# MCU009B_Xds100v2Emu.net
KiCad netlist of a schematic drawn in Altium Designer
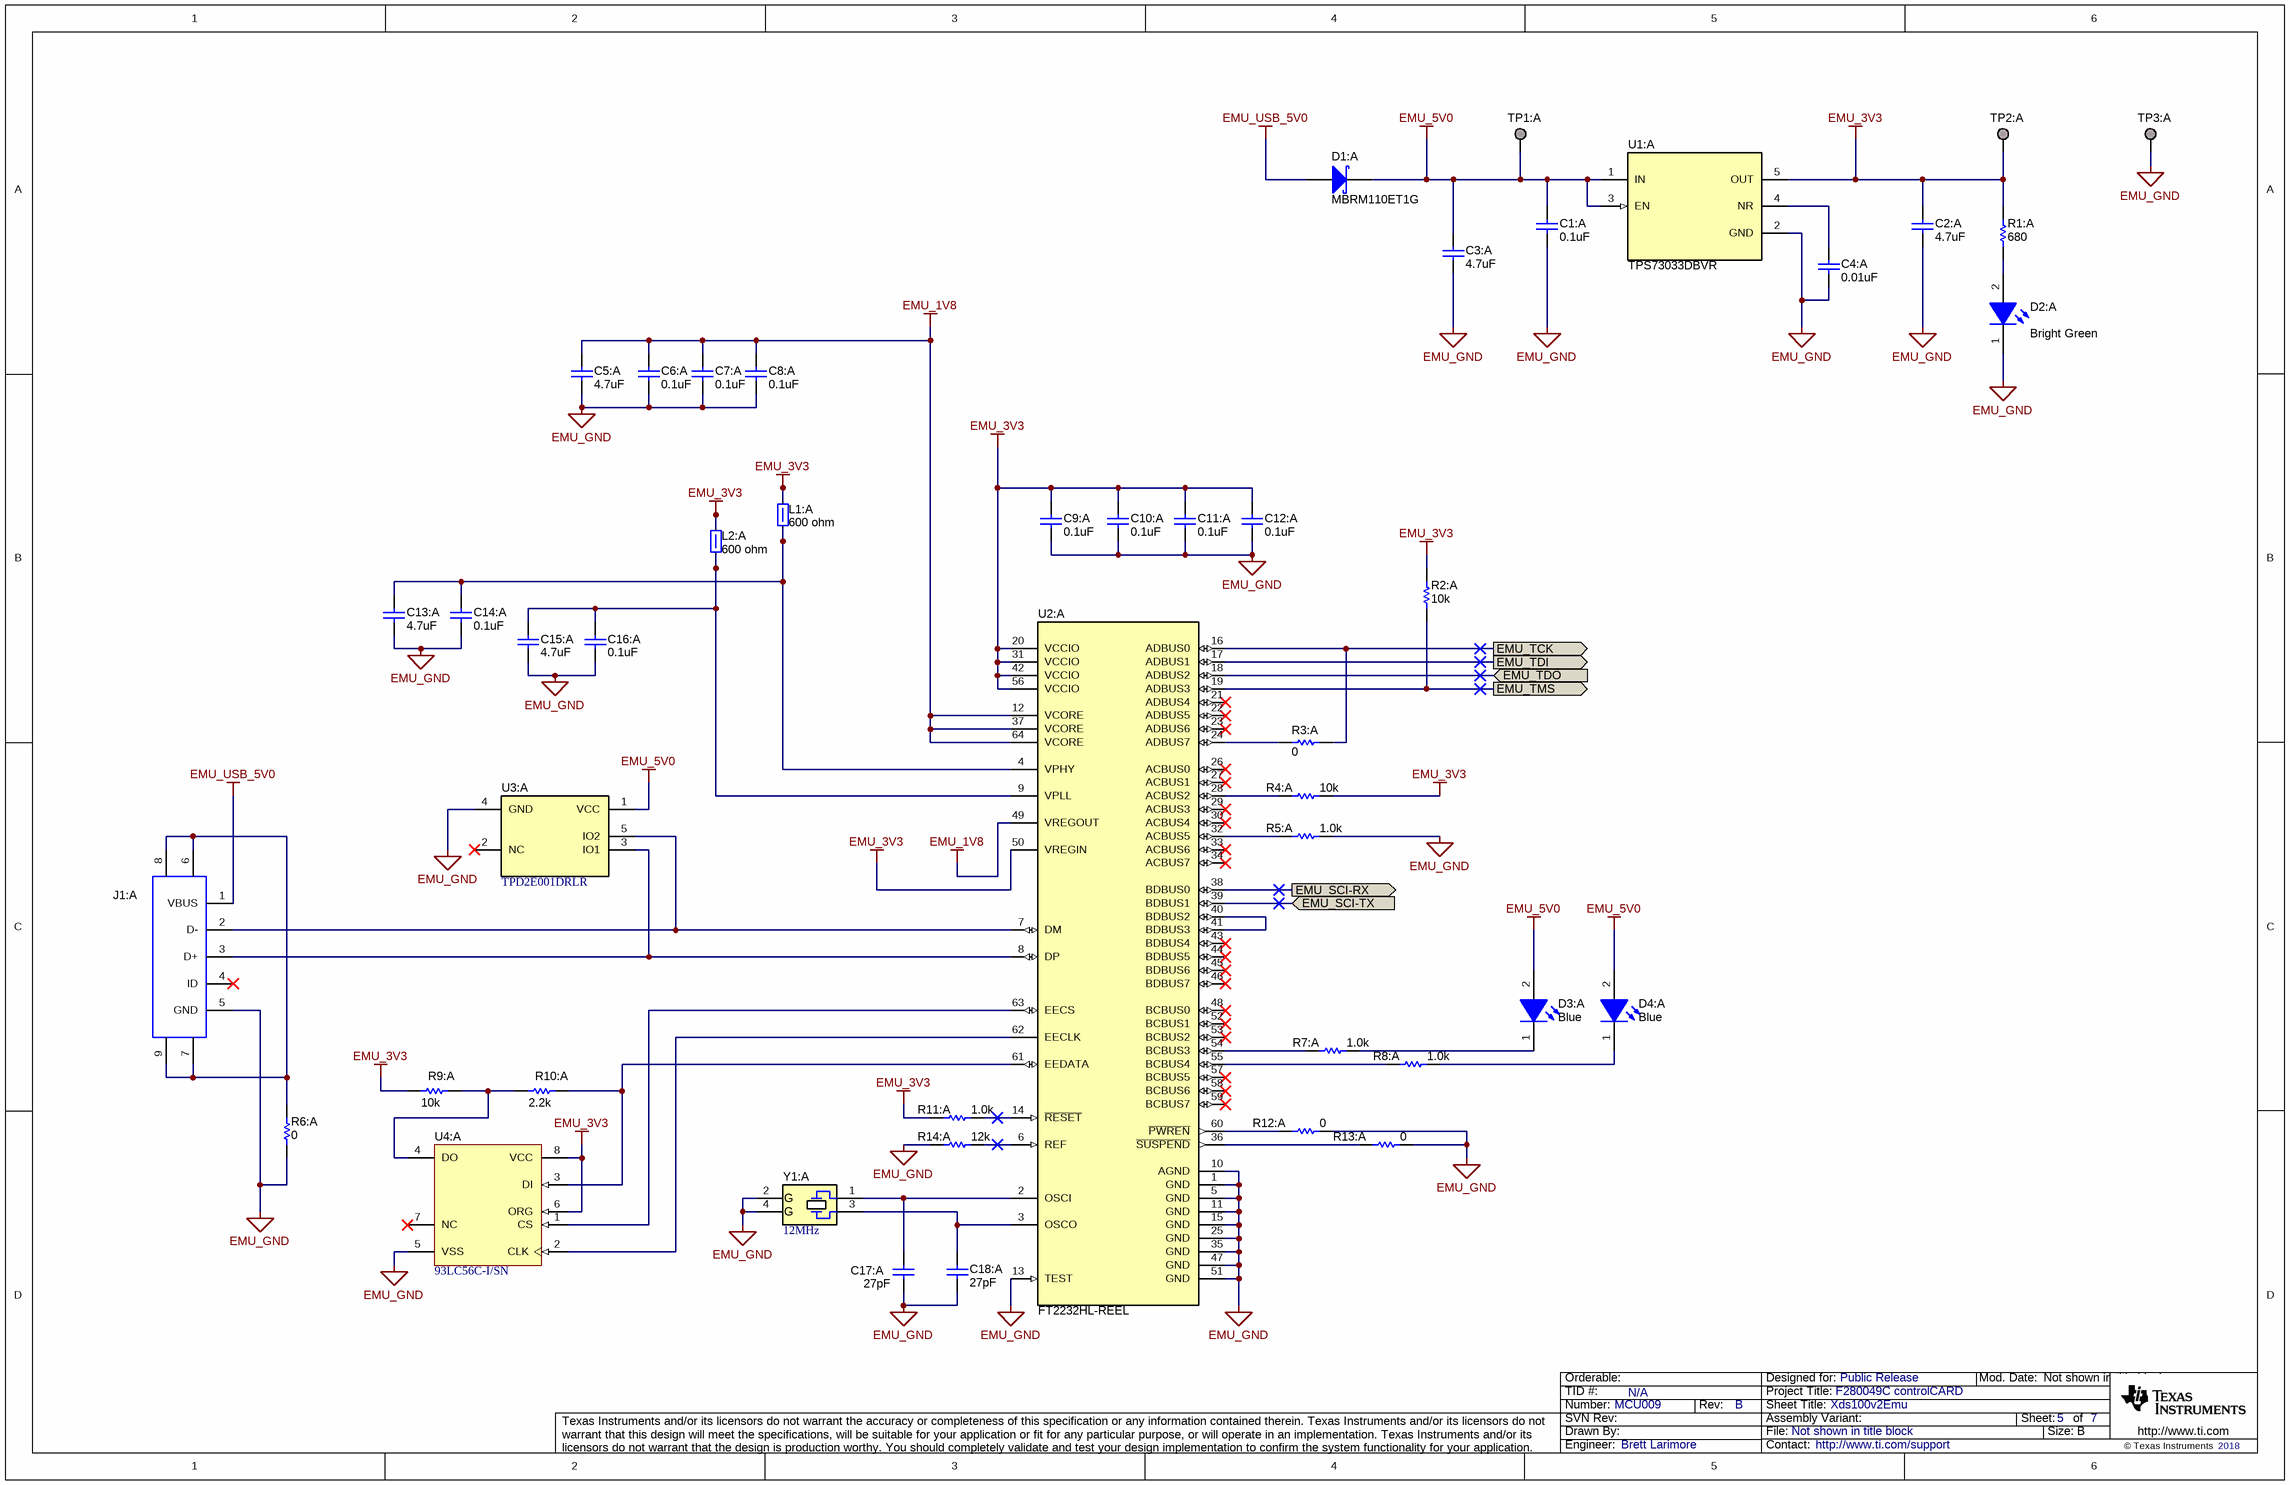
[diagram p0: MCU009B_Xds100v2Emu.SchDoc]

(export (version "E")
  (design (tool "Eeschema 10.0.6"))
  (components
    (comp (ref "C1:A")
      (value "GRM155R71A104KA01D")
      (footprint "0402")
      (description "CAP, CERM, 0.1 uF, 10 V, +/- 10%, X7R, 0402")
      (fields
        (field (name "VALUEDISPLAYED") "0.1uF")
        (field (name "MANUFACTURER") "MuRata")
        (field (name "PUBLISHER") "Texas Instruments")
      )
      (libsource (lib "Altium Vault - TI") (part "Capacitor"))
    )
    (comp (ref "C2:A")
      (value "GRM188R60J475ME19D")
      (footprint "0603")
      (description "CAP, CERM, 4.7 uF, 6.3 V, +/- 20%, X5R, 0603")
      (fields
        (field (name "VALUEDISPLAYED") "4.7uF")
        (field (name "MANUFACTURER") "MuRata")
        (field (name "PUBLISHER") "Texas Instruments")
      )
      (libsource (lib "Altium Vault - TI") (part "Capacitor"))
    )
    (comp (ref "C3:A")
      (value "GRM188R60J475ME19D")
      (footprint "0603")
      (description "CAP, CERM, 4.7 uF, 6.3 V, +/- 20%, X5R, 0603")
      (fields
        (field (name "VALUEDISPLAYED") "4.7uF")
        (field (name "MANUFACTURER") "MuRata")
        (field (name "PUBLISHER") "Texas Instruments")
      )
      (libsource (lib "Altium Vault - TI") (part "Capacitor"))
    )
    (comp (ref "C4:A")
      (value "GRM155R71C103KA01D")
      (footprint "0402")
      (description "CAP, CERM, 0.01 uF, 16 V, +/- 10%, X7R, 0402")
      (fields
        (field (name "VALUEDISPLAYED") "0.01uF")
        (field (name "MANUFACTURER") "MuRata")
        (field (name "PUBLISHER") "Texas Instruments")
      )
      (libsource (lib "Altium Vault - TI") (part "Capacitor"))
    )
    (comp (ref "C5:A")
      (value "GRM188R60J475ME19D")
      (footprint "0603")
      (description "CAP, CERM, 4.7 uF, 6.3 V, +/- 20%, X5R, 0603")
      (fields
        (field (name "VALUEDISPLAYED") "4.7uF")
        (field (name "MANUFACTURER") "MuRata")
        (field (name "PUBLISHER") "Texas Instruments")
      )
      (libsource (lib "Altium Vault - TI") (part "Capacitor"))
    )
    (comp (ref "C6:A")
      (value "GRM155R71A104KA01D")
      (footprint "0402")
      (description "CAP, CERM, 0.1 uF, 10 V, +/- 10%, X7R, 0402")
      (fields
        (field (name "VALUEDISPLAYED") "0.1uF")
        (field (name "MANUFACTURER") "MuRata")
        (field (name "PUBLISHER") "Texas Instruments")
      )
      (libsource (lib "Altium Vault - TI") (part "Capacitor"))
    )
    (comp (ref "C7:A")
      (value "GRM155R71A104KA01D")
      (footprint "0402")
      (description "CAP, CERM, 0.1 uF, 10 V, +/- 10%, X7R, 0402")
      (fields
        (field (name "VALUEDISPLAYED") "0.1uF")
        (field (name "MANUFACTURER") "MuRata")
        (field (name "PUBLISHER") "Texas Instruments")
      )
      (libsource (lib "Altium Vault - TI") (part "Capacitor"))
    )
    (comp (ref "C8:A")
      (value "GRM155R71A104KA01D")
      (footprint "0402")
      (description "CAP, CERM, 0.1 uF, 10 V, +/- 10%, X7R, 0402")
      (fields
        (field (name "VALUEDISPLAYED") "0.1uF")
        (field (name "MANUFACTURER") "MuRata")
        (field (name "PUBLISHER") "Texas Instruments")
      )
      (libsource (lib "Altium Vault - TI") (part "Capacitor"))
    )
    (comp (ref "C9:A")
      (value "GRM155R71A104KA01D")
      (footprint "0402")
      (description "CAP, CERM, 0.1 uF, 10 V, +/- 10%, X7R, 0402")
      (fields
        (field (name "VALUEDISPLAYED") "0.1uF")
        (field (name "MANUFACTURER") "MuRata")
        (field (name "PUBLISHER") "Texas Instruments")
      )
      (libsource (lib "Altium Vault - TI") (part "Capacitor"))
    )
    (comp (ref "C10:A")
      (value "GRM155R71A104KA01D")
      (footprint "0402")
      (description "CAP, CERM, 0.1 uF, 10 V, +/- 10%, X7R, 0402")
      (fields
        (field (name "VALUEDISPLAYED") "0.1uF")
        (field (name "MANUFACTURER") "MuRata")
        (field (name "PUBLISHER") "Texas Instruments")
      )
      (libsource (lib "Altium Vault - TI") (part "Capacitor"))
    )
    (comp (ref "C11:A")
      (value "GRM155R71A104KA01D")
      (footprint "0402")
      (description "CAP, CERM, 0.1 uF, 10 V, +/- 10%, X7R, 0402")
      (fields
        (field (name "VALUEDISPLAYED") "0.1uF")
        (field (name "MANUFACTURER") "MuRata")
        (field (name "PUBLISHER") "Texas Instruments")
      )
      (libsource (lib "Altium Vault - TI") (part "Capacitor"))
    )
    (comp (ref "C12:A")
      (value "GRM155R71A104KA01D")
      (footprint "0402")
      (description "CAP, CERM, 0.1 uF, 10 V, +/- 10%, X7R, 0402")
      (fields
        (field (name "VALUEDISPLAYED") "0.1uF")
        (field (name "MANUFACTURER") "MuRata")
        (field (name "PUBLISHER") "Texas Instruments")
      )
      (libsource (lib "Altium Vault - TI") (part "Capacitor"))
    )
    (comp (ref "C13:A")
      (value "GRM188R60J475ME19D")
      (footprint "0603")
      (description "CAP, CERM, 4.7 uF, 6.3 V, +/- 20%, X5R, 0603")
      (fields
        (field (name "VALUEDISPLAYED") "4.7uF")
        (field (name "MANUFACTURER") "MuRata")
        (field (name "PUBLISHER") "Texas Instruments")
      )
      (libsource (lib "Altium Vault - TI") (part "Capacitor"))
    )
    (comp (ref "C14:A")
      (value "GRM155R71A104KA01D")
      (footprint "0402")
      (description "CAP, CERM, 0.1 uF, 10 V, +/- 10%, X7R, 0402")
      (fields
        (field (name "VALUEDISPLAYED") "0.1uF")
        (field (name "MANUFACTURER") "MuRata")
        (field (name "PUBLISHER") "Texas Instruments")
      )
      (libsource (lib "Altium Vault - TI") (part "Capacitor"))
    )
    (comp (ref "C15:A")
      (value "GRM188R60J475ME19D")
      (footprint "0603")
      (description "CAP, CERM, 4.7 uF, 6.3 V, +/- 20%, X5R, 0603")
      (fields
        (field (name "VALUEDISPLAYED") "4.7uF")
        (field (name "MANUFACTURER") "MuRata")
        (field (name "PUBLISHER") "Texas Instruments")
      )
      (libsource (lib "Altium Vault - TI") (part "Capacitor"))
    )
    (comp (ref "C16:A")
      (value "GRM155R71A104KA01D")
      (footprint "0402")
      (description "CAP, CERM, 0.1 uF, 10 V, +/- 10%, X7R, 0402")
      (fields
        (field (name "VALUEDISPLAYED") "0.1uF")
        (field (name "MANUFACTURER") "MuRata")
        (field (name "PUBLISHER") "Texas Instruments")
      )
      (libsource (lib "Altium Vault - TI") (part "Capacitor"))
    )
    (comp (ref "C17:A")
      (value "GRM1555C1H270JA01D")
      (footprint "0402")
      (description "CAP, CERM, 27 pF, 50 V, +/- 5%, C0G/NP0, 0402")
      (fields
        (field (name "VALUEDISPLAYED") "27pF")
        (field (name "MANUFACTURER") "MuRata")
        (field (name "PUBLISHER") "Texas Instruments")
      )
      (libsource (lib "Altium Vault - TI") (part "Capacitor"))
    )
    (comp (ref "C18:A")
      (value "GRM1555C1H270JA01D")
      (footprint "0402")
      (description "CAP, CERM, 27 pF, 50 V, +/- 5%, C0G/NP0, 0402")
      (fields
        (field (name "VALUEDISPLAYED") "27pF")
        (field (name "MANUFACTURER") "MuRata")
        (field (name "PUBLISHER") "Texas Instruments")
      )
      (libsource (lib "Altium Vault - TI") (part "Capacitor"))
    )
    (comp (ref "D1:A")
      (value "MBRM110ET1G")
      (footprint "POWERMITE")
      (description "Diode, Schottky, 10 V, 1 A, AEC-Q101, POWERMITE")
      (fields (field (name "MANUFACTURER") "ON Semiconductor") (field (name "PUBLISHER") "Texas Instruments"))
      (libsource (lib "Altium Vault - TI") (part "DIODE_SCHOTTKY"))
    )
    (comp (ref "D2:A")
      (value "Bright Green")
      (footprint "WL-SMCW_Green_0805")
      (description "LED, Bright Green, SMD")
      (fields
        (field (name "PARTNUMBER") "150080VS75000")
        (field (name "MANUFACTURER") "Wurth Elektronik")
        (field (name "PUBLISHER") "Texas Instruments")
      )
      (libsource (lib "Altium Vault - TI") (part "LED_A2_K1"))
    )
    (comp (ref "D3:A")
      (value "Blue")
      (footprint "WL-SMCW_Blue_0805")
      (description "LED, Blue, SMD")
      (fields
        (field (name "MANUFACTURER") "Wurth Elektronik")
        (field (name "PARTNUMBER") "150080BS75000")
        (field (name "PUBLISHER") "Texas Instruments")
      )
      (libsource (lib "Altium Vault - TI") (part "LED_A2_K1"))
    )
    (comp (ref "D4:A")
      (value "Blue")
      (footprint "WL-SMCW_Blue_0805")
      (description "LED, Blue, SMD")
      (fields
        (field (name "MANUFACTURER") "Wurth Elektronik")
        (field (name "PARTNUMBER") "150080BS75000")
        (field (name "PUBLISHER") "Texas Instruments")
      )
      (libsource (lib "Altium Vault - TI") (part "LED_A2_K1"))
    )
    (comp (ref "J1:A")
      (value "65100516121")
      (footprint "Wurth_65100516121")
      (description "Connector, Receptacle, USB Mini B 2.0, SMT")
      (fields (field (name "MANUFACTURER") "Wurth Elektronik") (field (name "PUBLISHER") "Texas Instruments"))
      (libsource (lib "Altium Vault - TI") (part "CONN_USB_5Pos-4Shld"))
    )
    (comp (ref "L1:A")
      (value "600 ohm")
      (footprint "0805_HV")
      (description "Ferrite Bead, 600 ohm @ 100 MHz, 0.5 A, 0805")
      (fields
        (field (name "PARTNUMBER") "HZ0805E601R-10")
        (field (name "MANUFACTURER") "Laird-Signal Integrity Products")
        (field (name "PUBLISHER") "Texas Instruments")
      )
      (libsource (lib "Altium Vault - TI") (part "Ferrite_Bead"))
    )
    (comp (ref "L2:A")
      (value "600 ohm")
      (footprint "0805_HV")
      (description "Ferrite Bead, 600 ohm @ 100 MHz, 0.5 A, 0805")
      (fields
        (field (name "PARTNUMBER") "HZ0805E601R-10")
        (field (name "MANUFACTURER") "Laird-Signal Integrity Products")
        (field (name "PUBLISHER") "Texas Instruments")
      )
      (libsource (lib "Altium Vault - TI") (part "Ferrite_Bead"))
    )
    (comp (ref "R1:A")
      (value "CRCW0402680RJNED")
      (footprint "0402")
      (description "RES, 680, 5%, 0.063 W, AEC-Q200 Grade 0, 0402")
      (fields (field (name "VALUEDISPLAYED") "680") (field (name "MANUFACTURER") "Vishay-Dale"))
      (libsource (lib "Altium Vault - TI") (part "Resistor"))
    )
    (comp (ref "R2:A")
      (value "CRCW040210K0JNED")
      (footprint "0402")
      (description "RES, 10 k, 5%, 0.063 W, AEC-Q200 Grade 0, 0402")
      (fields (field (name "VALUEDISPLAYED") "10k") (field (name "MANUFACTURER") "Vishay-Dale"))
      (libsource (lib "Altium Vault - TI") (part "Resistor"))
    )
    (comp (ref "R3:A")
      (value "CRCW04020000Z0ED")
      (footprint "0402")
      (description "RES, 0, 5%, 0.063 W, AEC-Q200 Grade 0, 0402")
      (fields (field (name "VALUEDISPLAYED") "0") (field (name "MANUFACTURER") "Vishay-Dale"))
      (libsource (lib "Altium Vault - TI") (part "Resistor"))
    )
    (comp (ref "R4:A")
      (value "CRCW040210K0JNED")
      (footprint "0402")
      (description "RES, 10 k, 5%, 0.063 W, AEC-Q200 Grade 0, 0402")
      (fields (field (name "VALUEDISPLAYED") "10k") (field (name "MANUFACTURER") "Vishay-Dale"))
      (libsource (lib "Altium Vault - TI") (part "Resistor"))
    )
    (comp (ref "R5:A")
      (value "CRCW04021K00JNED")
      (footprint "0402")
      (description "RES, 1.0 k, 5%, 0.063 W, AEC-Q200 Grade 0, 0402")
      (fields (field (name "VALUEDISPLAYED") "1.0k") (field (name "MANUFACTURER") "Vishay-Dale"))
      (libsource (lib "Altium Vault - TI") (part "Resistor"))
    )
    (comp (ref "R6:A")
      (value "CRCW04020000Z0ED")
      (footprint "0402")
      (description "RES, 0, 5%, 0.063 W, AEC-Q200 Grade 0, 0402")
      (fields (field (name "VALUEDISPLAYED") "0") (field (name "MANUFACTURER") "Vishay-Dale"))
      (libsource (lib "Altium Vault - TI") (part "Resistor"))
    )
    (comp (ref "R7:A")
      (value "CRCW04021K00JNED")
      (footprint "0402")
      (description "RES, 1.0 k, 5%, 0.063 W, AEC-Q200 Grade 0, 0402")
      (fields (field (name "VALUEDISPLAYED") "1.0k") (field (name "MANUFACTURER") "Vishay-Dale"))
      (libsource (lib "Altium Vault - TI") (part "Resistor"))
    )
    (comp (ref "R8:A")
      (value "CRCW04021K00JNED")
      (footprint "0402")
      (description "RES, 1.0 k, 5%, 0.063 W, AEC-Q200 Grade 0, 0402")
      (fields (field (name "VALUEDISPLAYED") "1.0k") (field (name "MANUFACTURER") "Vishay-Dale"))
      (libsource (lib "Altium Vault - TI") (part "Resistor"))
    )
    (comp (ref "R9:A")
      (value "CRCW040210K0JNED")
      (footprint "0402")
      (description "RES, 10 k, 5%, 0.063 W, AEC-Q200 Grade 0, 0402")
      (fields (field (name "VALUEDISPLAYED") "10k") (field (name "MANUFACTURER") "Vishay-Dale"))
      (libsource (lib "Altium Vault - TI") (part "Resistor"))
    )
    (comp (ref "R10:A")
      (value "CRCW04022K20JNED")
      (footprint "0402")
      (description "RES, 2.2 k, 5%, 0.063 W, AEC-Q200 Grade 0, 0402")
      (fields (field (name "VALUEDISPLAYED") "2.2k") (field (name "MANUFACTURER") "Vishay-Dale"))
      (libsource (lib "Altium Vault - TI") (part "Resistor"))
    )
    (comp (ref "R11:A")
      (value "CRCW04021K00JNED")
      (footprint "0402")
      (description "RES, 1.0 k, 5%, 0.063 W, AEC-Q200 Grade 0, 0402")
      (fields (field (name "VALUEDISPLAYED") "1.0k") (field (name "MANUFACTURER") "Vishay-Dale"))
      (libsource (lib "Altium Vault - TI") (part "Resistor"))
    )
    (comp (ref "R12:A")
      (value "CRCW04020000Z0ED")
      (footprint "0402")
      (description "RES, 0, 5%, 0.063 W, AEC-Q200 Grade 0, 0402")
      (fields (field (name "VALUEDISPLAYED") "0") (field (name "MANUFACTURER") "Vishay-Dale"))
      (libsource (lib "Altium Vault - TI") (part "Resistor"))
    )
    (comp (ref "R13:A")
      (value "CRCW04020000Z0ED")
      (footprint "0402")
      (description "RES, 0, 5%, 0.063 W, AEC-Q200 Grade 0, 0402")
      (fields (field (name "VALUEDISPLAYED") "0") (field (name "MANUFACTURER") "Vishay-Dale"))
      (libsource (lib "Altium Vault - TI") (part "Resistor"))
    )
    (comp (ref "R14:A")
      (value "CRCW040212K0JNED")
      (footprint "0402")
      (description "RES, 12 k, 5%, 0.063 W, AEC-Q200 Grade 0, 0402")
      (fields (field (name "VALUEDISPLAYED") "12k") (field (name "MANUFACTURER") "Vishay-Dale"))
      (libsource (lib "Altium Vault - TI") (part "Resistor"))
    )
    (comp (ref "TP1:A")
      (value "TESTPOINT")
      (footprint "TP_50MIL-25MILHOLE")
      (description "TEST POINT.  No entry in BOM.")
      (libsource (lib "Altium Vault - TI") (part "TESTPOINT"))
    )
    (comp (ref "TP2:A")
      (value "TESTPOINT")
      (footprint "TP_50MIL-25MILHOLE")
      (description "TEST POINT.  No entry in BOM.")
      (libsource (lib "Altium Vault - TI") (part "TESTPOINT"))
    )
    (comp (ref "TP3:A")
      (value "TESTPOINT")
      (footprint "TP_50MIL-25MILHOLE")
      (description "TEST POINT.  No entry in BOM.")
      (libsource (lib "Altium Vault - TI") (part "TESTPOINT"))
    )
    (comp (ref "U1:A")
      (value "TPS73033DBVR")
      (footprint "DBV0005A_N")
      (description "Low-Noise, High PSRR, RF 200-mA Low-Dropout Linear Regulators, DBV0005A (SOT-23-5)")
      (fields
        (field (name "ALTERNATE PARTNUMBER") "TPS73033DBVT")
        (field (name "MANUFACTURER") "Texas Instruments")
        (field (name "PUBLISHER") "Texas Instruments")
      )
      (libsource (lib "Altium Vault - TI") (part "TPS730XXDBV"))
    )
    (comp (ref "U2:A")
      (value "FT2232HL-REEL")
      (footprint "LQFP64_N")
      (description "Dual High Speed USB To Multipurpose UART/FIFO IC, LQFP-64")
      (fields (field (name "MANUFACTURER") "FTDI") (field (name "PUBLISHER") "Texas Instruments"))
      (libsource (lib "Altium Vault - TI") (part "FT2232H"))
    )
    (comp (ref "U3:A")
      (value "TPD2E001DRLR")
      (footprint "DRL0005A")
      (fields (field (name "MANUFACTURER") "Texas Instruments"))
      (libsource (lib "Altium Vault - TI") (part "TI-TPD2E001-Q1-SOT_DRL-5"))
    )
    (comp (ref "U4:A")
      (value "93LC56C-I/SN")
      (footprint "SOIC-8")
      (description "2K Microwire Compatible Serial EEPROM, SOIC-8")
      (fields (field (name "MANUFACTURER") "Microchip") (field (name "PUBLISHER") "Texas Instruments"))
      (libsource (lib "Altium Vault - TI") (part "93LC46C-SN"))
    )
    (comp (ref "Y1:A")
      (value "12MHz")
      (footprint "ECS_ECX-53B")
      (description "Crystal, 12 MHz, 20pF, SMD")
      (fields (field (name "PARTNUMBER") "ECS-120-20-30B-TR") (field (name "MANUFACTURER") "ECS Inc."))
      (libsource (lib "Altium Vault - TI") (part "CMP-0004646-3"))
    )
  )
  (nets
    (net (code "1") (name "/EMU_SCI-RX") (class "Default")
      (node (ref "U2:A") (pin "38") (pinfunction "BDBUS0_38") (pintype "bidirectional"))
    )
    (net (code "2") (name "/EMU_SCI-TX") (class "Default")
      (node (ref "U2:A") (pin "39") (pinfunction "BDBUS1_39") (pintype "bidirectional"))
    )
    (net (code "3") (name "/EMU_TCK") (class "Default")
      (node (ref "R3:A") (pin "1") (pinfunction "1_1") (pintype "passive"))
      (node (ref "U2:A") (pin "16") (pinfunction "ADBUS0_16") (pintype "bidirectional"))
    )
    (net (code "4") (name "/EMU_TDI") (class "Default")
      (node (ref "U2:A") (pin "17") (pinfunction "ADBUS1_17") (pintype "bidirectional"))
    )
    (net (code "5") (name "/EMU_TDO") (class "Default")
      (node (ref "U2:A") (pin "18") (pinfunction "ADBUS2_18") (pintype "bidirectional"))
    )
    (net (code "6") (name "/EMU_TMS") (class "Default")
      (node (ref "R2:A") (pin "1") (pinfunction "1_1") (pintype "passive"))
      (node (ref "U2:A") (pin "19") (pinfunction "ADBUS3_19") (pintype "bidirectional"))
    )
    (net (code "7") (name "EMU_1V8") (class "Default")
      (node (ref "C5:A") (pin "2") (pinfunction "2_2") (pintype "passive"))
      (node (ref "C6:A") (pin "2") (pinfunction "2_2") (pintype "passive"))
      (node (ref "C7:A") (pin "2") (pinfunction "2_2") (pintype "passive"))
      (node (ref "C8:A") (pin "2") (pinfunction "2_2") (pintype "passive"))
      (node (ref "U2:A") (pin "12") (pinfunction "VCORE_12") (pintype "power_in"))
      (node (ref "U2:A") (pin "37") (pinfunction "VCORE_37") (pintype "power_in"))
      (node (ref "U2:A") (pin "49") (pinfunction "VREGOUT_49") (pintype "power_in"))
      (node (ref "U2:A") (pin "64") (pinfunction "VCORE_64") (pintype "power_in"))
    )
    (net (code "8") (name "EMU_3V3") (class "Default")
      (node (ref "C10:A") (pin "2") (pinfunction "2_2") (pintype "passive"))
      (node (ref "C11:A") (pin "2") (pinfunction "2_2") (pintype "passive"))
      (node (ref "C12:A") (pin "2") (pinfunction "2_2") (pintype "passive"))
      (node (ref "C2:A") (pin "1") (pinfunction "1_1") (pintype "passive"))
      (node (ref "C9:A") (pin "2") (pinfunction "2_2") (pintype "passive"))
      (node (ref "L1:A") (pin "2") (pinfunction "2_2") (pintype "passive"))
      (node (ref "L2:A") (pin "2") (pinfunction "2_2") (pintype "passive"))
      (node (ref "R11:A") (pin "1") (pinfunction "1_1") (pintype "passive"))
      (node (ref "R1:A") (pin "1") (pinfunction "1_1") (pintype "passive"))
      (node (ref "R2:A") (pin "2") (pinfunction "2_2") (pintype "passive"))
      (node (ref "R4:A") (pin "2") (pinfunction "2_2") (pintype "passive"))
      (node (ref "R9:A") (pin "1") (pinfunction "1_1") (pintype "passive"))
      (node (ref "TP2:A") (pin "1") (pintype "passive"))
      (node (ref "U1:A") (pin "5") (pinfunction "OUT_5") (pintype "power_in"))
      (node (ref "U2:A") (pin "20") (pinfunction "VCCIO_20") (pintype "power_in"))
      (node (ref "U2:A") (pin "31") (pinfunction "VCCIO_31") (pintype "power_in"))
      (node (ref "U2:A") (pin "42") (pinfunction "VCCIO_42") (pintype "power_in"))
      (node (ref "U2:A") (pin "50") (pinfunction "VREGIN_50") (pintype "power_in"))
      (node (ref "U2:A") (pin "56") (pinfunction "VCCIO_56") (pintype "power_in"))
      (node (ref "U4:A") (pin "6") (pinfunction "ORG_6") (pintype "input"))
      (node (ref "U4:A") (pin "8") (pinfunction "VCC_8") (pintype "power_in"))
    )
    (net (code "9") (name "EMU_5V0") (class "Default")
      (node (ref "C1:A") (pin "2") (pinfunction "2_2") (pintype "passive"))
      (node (ref "C3:A") (pin "1") (pinfunction "1_1") (pintype "passive"))
      (node (ref "D1:A") (pin "1") (pinfunction "K_1") (pintype "passive"))
      (node (ref "D3:A") (pin "2") (pinfunction "A_2") (pintype "passive"))
      (node (ref "D4:A") (pin "2") (pinfunction "A_2") (pintype "passive"))
      (node (ref "TP1:A") (pin "1") (pintype "passive"))
      (node (ref "U1:A") (pin "1") (pinfunction "IN_1") (pintype "power_in"))
      (node (ref "U1:A") (pin "3") (pinfunction "EN_3") (pintype "input"))
      (node (ref "U3:A") (pin "1") (pinfunction "VCC_1") (pintype "power_in"))
    )
    (net (code "10") (name "EMU_GND") (class "Default")
      (node (ref "C10:A") (pin "1") (pinfunction "1_1") (pintype "passive"))
      (node (ref "C11:A") (pin "1") (pinfunction "1_1") (pintype "passive"))
      (node (ref "C12:A") (pin "1") (pinfunction "1_1") (pintype "passive"))
      (node (ref "C13:A") (pin "2") (pinfunction "2_2") (pintype "passive"))
      (node (ref "C14:A") (pin "1") (pinfunction "1_1") (pintype "passive"))
      (node (ref "C15:A") (pin "2") (pinfunction "2_2") (pintype "passive"))
      (node (ref "C16:A") (pin "1") (pinfunction "1_1") (pintype "passive"))
      (node (ref "C17:A") (pin "1") (pinfunction "1_1") (pintype "passive"))
      (node (ref "C18:A") (pin "1") (pinfunction "1_1") (pintype "passive"))
      (node (ref "C1:A") (pin "1") (pinfunction "1_1") (pintype "passive"))
      (node (ref "C2:A") (pin "2") (pinfunction "2_2") (pintype "passive"))
      (node (ref "C3:A") (pin "2") (pinfunction "2_2") (pintype "passive"))
      (node (ref "C4:A") (pin "1") (pinfunction "1_1") (pintype "passive"))
      (node (ref "C5:A") (pin "1") (pinfunction "1_1") (pintype "passive"))
      (node (ref "C6:A") (pin "1") (pinfunction "1_1") (pintype "passive"))
      (node (ref "C7:A") (pin "1") (pinfunction "1_1") (pintype "passive"))
      (node (ref "C8:A") (pin "1") (pinfunction "1_1") (pintype "passive"))
      (node (ref "C9:A") (pin "1") (pinfunction "1_1") (pintype "passive"))
      (node (ref "D2:A") (pin "1") (pinfunction "K_1") (pintype "passive"))
      (node (ref "J1:A") (pin "5") (pinfunction "GND_5") (pintype "passive"))
      (node (ref "R12:A") (pin "1") (pinfunction "1_1") (pintype "passive"))
      (node (ref "R13:A") (pin "1") (pinfunction "1_1") (pintype "passive"))
      (node (ref "R14:A") (pin "1") (pinfunction "1_1") (pintype "passive"))
      (node (ref "R5:A") (pin "2") (pinfunction "2_2") (pintype "passive"))
      (node (ref "R6:A") (pin "2") (pinfunction "2_2") (pintype "passive"))
      (node (ref "TP3:A") (pin "1") (pintype "passive"))
      (node (ref "U1:A") (pin "2") (pinfunction "GND_2") (pintype "power_in"))
      (node (ref "U2:A") (pin "1") (pinfunction "GND_1") (pintype "power_in"))
      (node (ref "U2:A") (pin "10") (pinfunction "AGND_10") (pintype "power_in"))
      (node (ref "U2:A") (pin "11") (pinfunction "GND_11") (pintype "power_in"))
      (node (ref "U2:A") (pin "13") (pinfunction "TEST_13") (pintype "input"))
      (node (ref "U2:A") (pin "15") (pinfunction "GND_15") (pintype "power_in"))
      (node (ref "U2:A") (pin "25") (pinfunction "GND_25") (pintype "power_in"))
      (node (ref "U2:A") (pin "35") (pinfunction "GND_35") (pintype "power_in"))
      (node (ref "U2:A") (pin "47") (pinfunction "GND_47") (pintype "power_in"))
      (node (ref "U2:A") (pin "5") (pinfunction "GND_5") (pintype "power_in"))
      (node (ref "U2:A") (pin "51") (pinfunction "GND_51") (pintype "power_in"))
      (node (ref "U3:A") (pin "4") (pinfunction "GND_4") (pintype "power_in"))
      (node (ref "U4:A") (pin "5") (pinfunction "VSS_5") (pintype "power_in"))
      (node (ref "Y1:A") (pin "2") (pinfunction "GND_2") (pintype "power_in"))
      (node (ref "Y1:A") (pin "4") (pinfunction "GND_4") (pintype "power_in"))
    )
    (net (code "11") (name "EMU_USB_5V0") (class "Default")
      (node (ref "D1:A") (pin "2") (pinfunction "A_2") (pintype "passive"))
      (node (ref "J1:A") (pin "1") (pinfunction "VBUS_1") (pintype "passive"))
    )
    (net (code "12") (name "Net-(D2:A-A)") (class "Default")
      (node (ref "D2:A") (pin "2") (pinfunction "A_2") (pintype "passive"))
      (node (ref "R1:A") (pin "2") (pinfunction "2_2") (pintype "passive"))
    )
    (net (code "13") (name "Net-(D3:A-K)") (class "Default")
      (node (ref "D3:A") (pin "1") (pinfunction "K_1") (pintype "passive"))
      (node (ref "R7:A") (pin "2") (pinfunction "2_2") (pintype "passive"))
    )
    (net (code "14") (name "Net-(D4:A-K)") (class "Default")
      (node (ref "D4:A") (pin "1") (pinfunction "K_1") (pintype "passive"))
      (node (ref "R8:A") (pin "2") (pinfunction "2_2") (pintype "passive"))
    )
    (net (code "15") (name "Net-(J1:A-D+)") (class "Default")
      (node (ref "J1:A") (pin "3") (pinfunction "D+_3") (pintype "passive"))
      (node (ref "U2:A") (pin "8") (pinfunction "DP_8") (pintype "bidirectional"))
      (node (ref "U3:A") (pin "3") (pinfunction "IO1_3") (pintype "passive"))
    )
    (net (code "16") (name "Net-(J1:A-D-)") (class "Default")
      (node (ref "J1:A") (pin "2") (pinfunction "D-_2") (pintype "passive"))
      (node (ref "U2:A") (pin "7") (pinfunction "DM_7") (pintype "bidirectional"))
      (node (ref "U3:A") (pin "5") (pinfunction "IO2_5") (pintype "passive"))
    )
    (net (code "17") (name "Net-(J1:A-Pad6)") (class "Default")
      (node (ref "J1:A") (pin "6") (pinfunction "6_6") (pintype "passive"))
      (node (ref "J1:A") (pin "7") (pinfunction "7_7") (pintype "passive"))
      (node (ref "J1:A") (pin "8") (pinfunction "8_8") (pintype "passive"))
      (node (ref "J1:A") (pin "9") (pinfunction "9_9") (pintype "passive"))
      (node (ref "R6:A") (pin "1") (pinfunction "1_1") (pintype "passive"))
    )
    (net (code "18") (name "Net-(U1:A-NR)") (class "Default")
      (node (ref "C4:A") (pin "2") (pinfunction "2_2") (pintype "passive"))
      (node (ref "U1:A") (pin "4") (pinfunction "NR_4") (pintype "passive"))
    )
    (net (code "19") (name "Net-(U2:A-ACBUS2)") (class "Default")
      (node (ref "R4:A") (pin "1") (pinfunction "1_1") (pintype "passive"))
      (node (ref "U2:A") (pin "28") (pinfunction "ACBUS2_28") (pintype "bidirectional"))
    )
    (net (code "20") (name "Net-(U2:A-ACBUS5)") (class "Default")
      (node (ref "R5:A") (pin "1") (pinfunction "1_1") (pintype "passive"))
      (node (ref "U2:A") (pin "32") (pinfunction "ACBUS5_32") (pintype "bidirectional"))
    )
    (net (code "21") (name "Net-(U2:A-ADBUS7)") (class "Default")
      (node (ref "R3:A") (pin "2") (pinfunction "2_2") (pintype "passive"))
      (node (ref "U2:A") (pin "24") (pinfunction "ADBUS7_24") (pintype "bidirectional"))
    )
    (net (code "22") (name "Net-(U2:A-BCBUS3)") (class "Default")
      (node (ref "R7:A") (pin "1") (pinfunction "1_1") (pintype "passive"))
      (node (ref "U2:A") (pin "54") (pinfunction "BCBUS3_54") (pintype "bidirectional"))
    )
    (net (code "23") (name "Net-(U2:A-BCBUS4)") (class "Default")
      (node (ref "R8:A") (pin "1") (pinfunction "1_1") (pintype "passive"))
      (node (ref "U2:A") (pin "55") (pinfunction "BCBUS4_55") (pintype "bidirectional"))
    )
    (net (code "24") (name "Net-(U2:A-BDBUS2)") (class "Default")
      (node (ref "U2:A") (pin "40") (pinfunction "BDBUS2_40") (pintype "bidirectional"))
      (node (ref "U2:A") (pin "41") (pinfunction "BDBUS3_41") (pintype "bidirectional"))
    )
    (net (code "25") (name "Net-(U2:A-EECLK)") (class "Default")
      (node (ref "U2:A") (pin "62") (pinfunction "EECLK_62") (pintype "tri_state"))
      (node (ref "U4:A") (pin "2") (pinfunction "CLK_2") (pintype "input"))
    )
    (net (code "26") (name "Net-(U2:A-EECS)") (class "Default")
      (node (ref "U2:A") (pin "63") (pinfunction "EECS_63") (pintype "bidirectional"))
      (node (ref "U4:A") (pin "1") (pinfunction "CS_1") (pintype "input"))
    )
    (net (code "27") (name "Net-(U2:A-EEDATA)") (class "Default")
      (node (ref "R10:A") (pin "2") (pinfunction "2_2") (pintype "passive"))
      (node (ref "U2:A") (pin "61") (pinfunction "EEDATA_61") (pintype "bidirectional"))
      (node (ref "U4:A") (pin "3") (pinfunction "DI_3") (pintype "input"))
    )
    (net (code "28") (name "Net-(U2:A-OSCI)") (class "Default")
      (node (ref "C17:A") (pin "2") (pinfunction "2_2") (pintype "passive"))
      (node (ref "U2:A") (pin "2") (pinfunction "OSCI_2") (pintype "passive"))
      (node (ref "Y1:A") (pin "1") (pinfunction "1_1") (pintype "passive"))
    )
    (net (code "29") (name "Net-(U2:A-OSCO)") (class "Default")
      (node (ref "C18:A") (pin "2") (pinfunction "2_2") (pintype "passive"))
      (node (ref "U2:A") (pin "3") (pinfunction "OSCO_3") (pintype "passive"))
      (node (ref "Y1:A") (pin "3") (pinfunction "3_3") (pintype "passive"))
    )
    (net (code "30") (name "Net-(U2:A-REF)") (class "Default")
      (node (ref "R14:A") (pin "2") (pinfunction "2_2") (pintype "passive"))
      (node (ref "U2:A") (pin "6") (pinfunction "REF_6") (pintype "input"))
    )
    (net (code "31") (name "Net-(U2:A-VPHY)") (class "Default")
      (node (ref "C13:A") (pin "1") (pinfunction "1_1") (pintype "passive"))
      (node (ref "C14:A") (pin "2") (pinfunction "2_2") (pintype "passive"))
      (node (ref "L1:A") (pin "1") (pinfunction "1_1") (pintype "passive"))
      (node (ref "U2:A") (pin "4") (pinfunction "VPHY_4") (pintype "power_in"))
    )
    (net (code "32") (name "Net-(U2:A-VPLL)") (class "Default")
      (node (ref "C15:A") (pin "1") (pinfunction "1_1") (pintype "passive"))
      (node (ref "C16:A") (pin "2") (pinfunction "2_2") (pintype "passive"))
      (node (ref "L2:A") (pin "1") (pinfunction "1_1") (pintype "passive"))
      (node (ref "U2:A") (pin "9") (pinfunction "VPLL_9") (pintype "power_in"))
    )
    (net (code "33") (name "Net-(U2:A-~{PWREN})") (class "Default")
      (node (ref "R12:A") (pin "2") (pinfunction "2_2") (pintype "passive"))
      (node (ref "U2:A") (pin "60") (pinfunction "~{PWREN}_60") (pintype "output"))
    )
    (net (code "34") (name "Net-(U2:A-~{RESET})") (class "Default")
      (node (ref "R11:A") (pin "2") (pinfunction "2_2") (pintype "passive"))
      (node (ref "U2:A") (pin "14") (pinfunction "~{RESET}_14") (pintype "input"))
    )
    (net (code "35") (name "Net-(U2:A-~{SUSPEND})") (class "Default")
      (node (ref "R13:A") (pin "2") (pinfunction "2_2") (pintype "passive"))
      (node (ref "U2:A") (pin "36") (pinfunction "~{SUSPEND}_36") (pintype "output"))
    )
    (net (code "36") (name "Net-(U4:A-DO)") (class "Default")
      (node (ref "R10:A") (pin "1") (pinfunction "1_1") (pintype "passive"))
      (node (ref "R9:A") (pin "2") (pinfunction "2_2") (pintype "passive"))
      (node (ref "U4:A") (pin "4") (pinfunction "DO_4") (pintype "tri_state"))
    )
    (net (code "37") (name "unconnected-(J1:A-ID-Pad4)") (class "Default")
      (node (ref "J1:A") (pin "4") (pinfunction "ID_4") (pintype "passive+no_connect"))
    )
    (net (code "38") (name "unconnected-(U2:A-ACBUS0-Pad26)") (class "Default")
      (node (ref "U2:A") (pin "26") (pinfunction "ACBUS0_26") (pintype "bidirectional+no_connect"))
    )
    (net (code "39") (name "unconnected-(U2:A-ACBUS1-Pad27)") (class "Default")
      (node (ref "U2:A") (pin "27") (pinfunction "ACBUS1_27") (pintype "bidirectional+no_connect"))
    )
    (net (code "40") (name "unconnected-(U2:A-ACBUS3-Pad29)") (class "Default")
      (node (ref "U2:A") (pin "29") (pinfunction "ACBUS3_29") (pintype "bidirectional+no_connect"))
    )
    (net (code "41") (name "unconnected-(U2:A-ACBUS4-Pad30)") (class "Default")
      (node (ref "U2:A") (pin "30") (pinfunction "ACBUS4_30") (pintype "bidirectional+no_connect"))
    )
    (net (code "42") (name "unconnected-(U2:A-ACBUS6-Pad33)") (class "Default")
      (node (ref "U2:A") (pin "33") (pinfunction "ACBUS6_33") (pintype "bidirectional+no_connect"))
    )
    (net (code "43") (name "unconnected-(U2:A-ACBUS7-Pad34)") (class "Default")
      (node (ref "U2:A") (pin "34") (pinfunction "ACBUS7_34") (pintype "bidirectional+no_connect"))
    )
    (net (code "44") (name "unconnected-(U2:A-ADBUS4-Pad21)") (class "Default")
      (node (ref "U2:A") (pin "21") (pinfunction "ADBUS4_21") (pintype "bidirectional+no_connect"))
    )
    (net (code "45") (name "unconnected-(U2:A-ADBUS5-Pad22)") (class "Default")
      (node (ref "U2:A") (pin "22") (pinfunction "ADBUS5_22") (pintype "bidirectional+no_connect"))
    )
    (net (code "46") (name "unconnected-(U2:A-ADBUS6-Pad23)") (class "Default")
      (node (ref "U2:A") (pin "23") (pinfunction "ADBUS6_23") (pintype "bidirectional+no_connect"))
    )
    (net (code "47") (name "unconnected-(U2:A-BCBUS0-Pad48)") (class "Default")
      (node (ref "U2:A") (pin "48") (pinfunction "BCBUS0_48") (pintype "bidirectional+no_connect"))
    )
    (net (code "48") (name "unconnected-(U2:A-BCBUS1-Pad52)") (class "Default")
      (node (ref "U2:A") (pin "52") (pinfunction "BCBUS1_52") (pintype "bidirectional+no_connect"))
    )
    (net (code "49") (name "unconnected-(U2:A-BCBUS2-Pad53)") (class "Default")
      (node (ref "U2:A") (pin "53") (pinfunction "BCBUS2_53") (pintype "bidirectional+no_connect"))
    )
    (net (code "50") (name "unconnected-(U2:A-BCBUS5-Pad57)") (class "Default")
      (node (ref "U2:A") (pin "57") (pinfunction "BCBUS5_57") (pintype "bidirectional+no_connect"))
    )
    (net (code "51") (name "unconnected-(U2:A-BCBUS6-Pad58)") (class "Default")
      (node (ref "U2:A") (pin "58") (pinfunction "BCBUS6_58") (pintype "bidirectional+no_connect"))
    )
    (net (code "52") (name "unconnected-(U2:A-BCBUS7-Pad59)") (class "Default")
      (node (ref "U2:A") (pin "59") (pinfunction "BCBUS7_59") (pintype "bidirectional+no_connect"))
    )
    (net (code "53") (name "unconnected-(U2:A-BDBUS4-Pad43)") (class "Default")
      (node (ref "U2:A") (pin "43") (pinfunction "BDBUS4_43") (pintype "bidirectional+no_connect"))
    )
    (net (code "54") (name "unconnected-(U2:A-BDBUS5-Pad44)") (class "Default")
      (node (ref "U2:A") (pin "44") (pinfunction "BDBUS5_44") (pintype "bidirectional+no_connect"))
    )
    (net (code "55") (name "unconnected-(U2:A-BDBUS6-Pad45)") (class "Default")
      (node (ref "U2:A") (pin "45") (pinfunction "BDBUS6_45") (pintype "bidirectional+no_connect"))
    )
    (net (code "56") (name "unconnected-(U2:A-BDBUS7-Pad46)") (class "Default")
      (node (ref "U2:A") (pin "46") (pinfunction "BDBUS7_46") (pintype "bidirectional+no_connect"))
    )
    (net (code "57") (name "unconnected-(U3:A-NC-Pad2)") (class "Default")
      (node (ref "U3:A") (pin "2") (pinfunction "NC_2") (pintype "passive+no_connect"))
    )
    (net (code "58") (name "unconnected-(U4:A-NC-Pad7)") (class "Default")
      (node (ref "U4:A") (pin "7") (pinfunction "NC_7") (pintype "passive+no_connect"))
    )
  )
)
